# HGD_MCU_v0_1_-20200807.net
KiCad netlist of a schematic drawn in Altium Designer
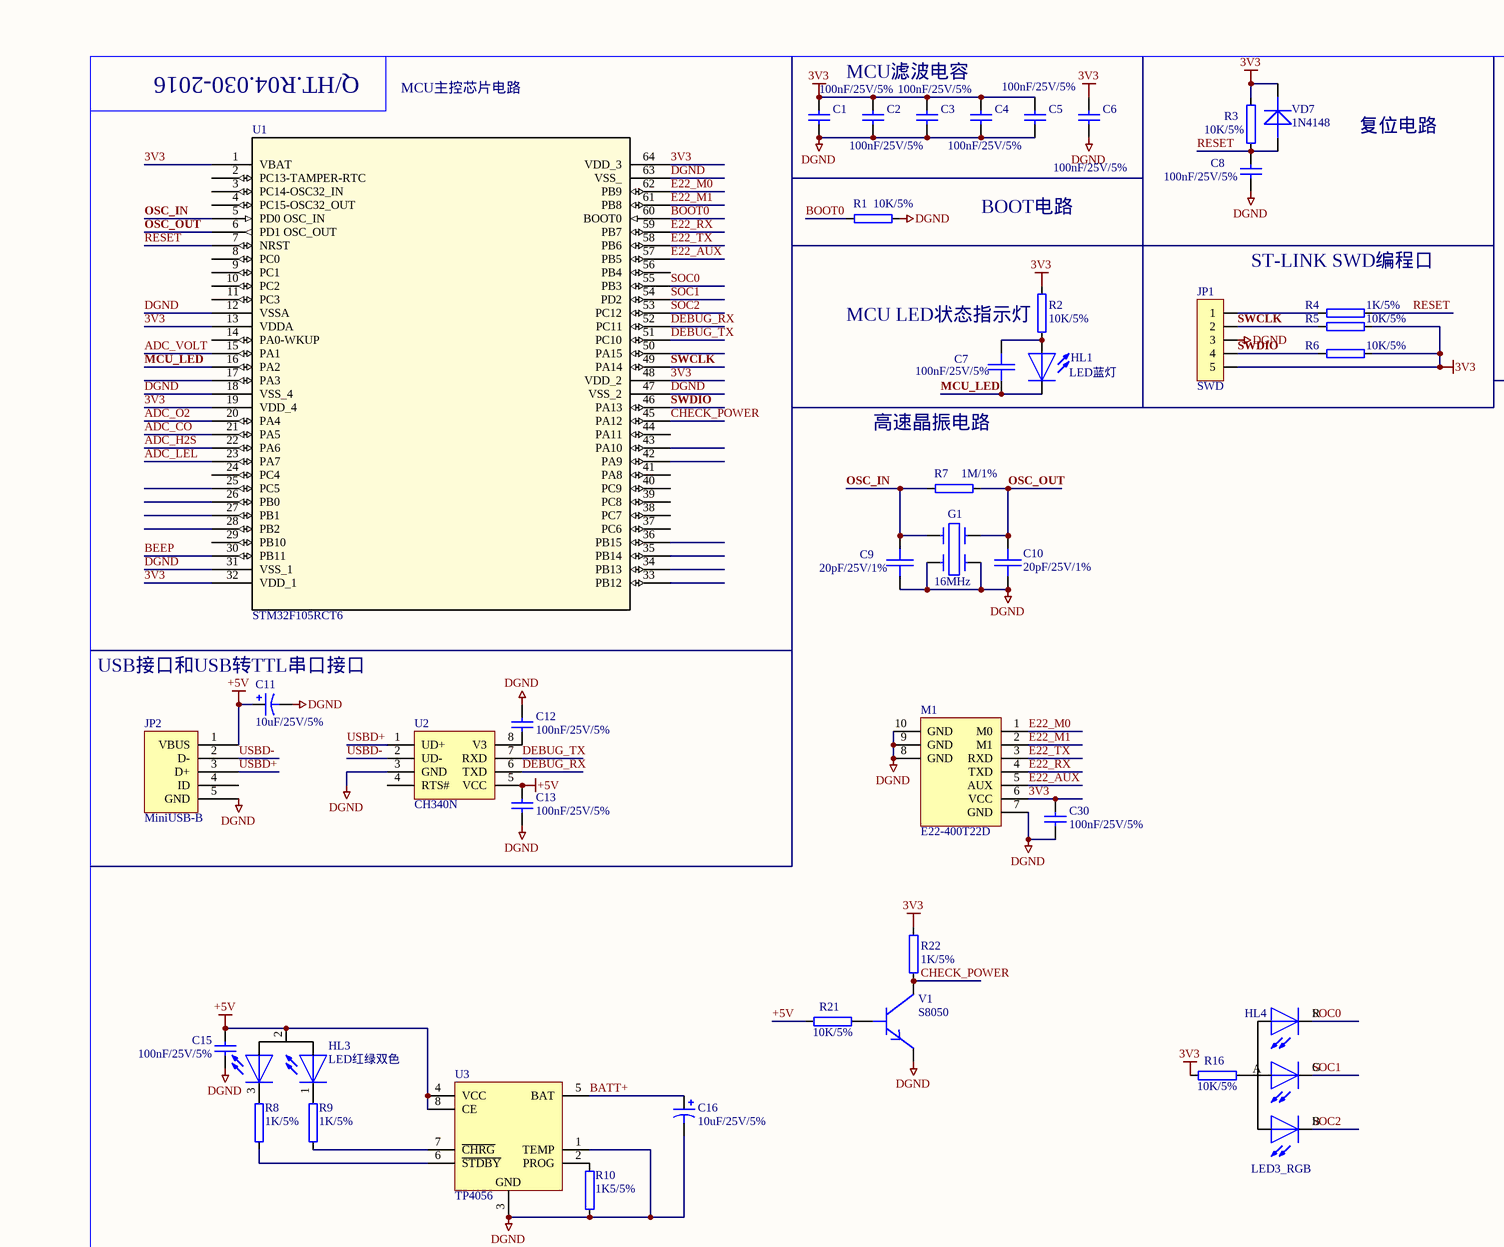
[diagram p0: HGD_MCU(v0.1)-20200807.SchDoc, top left]
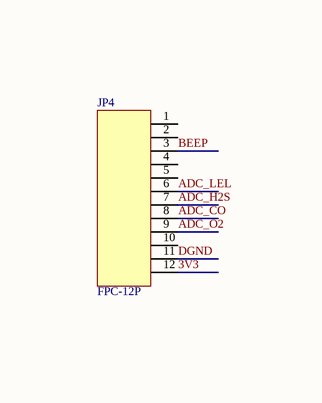
[diagram p1: HGD_MCU(v0.1)-20200807.SchDoc, top right]
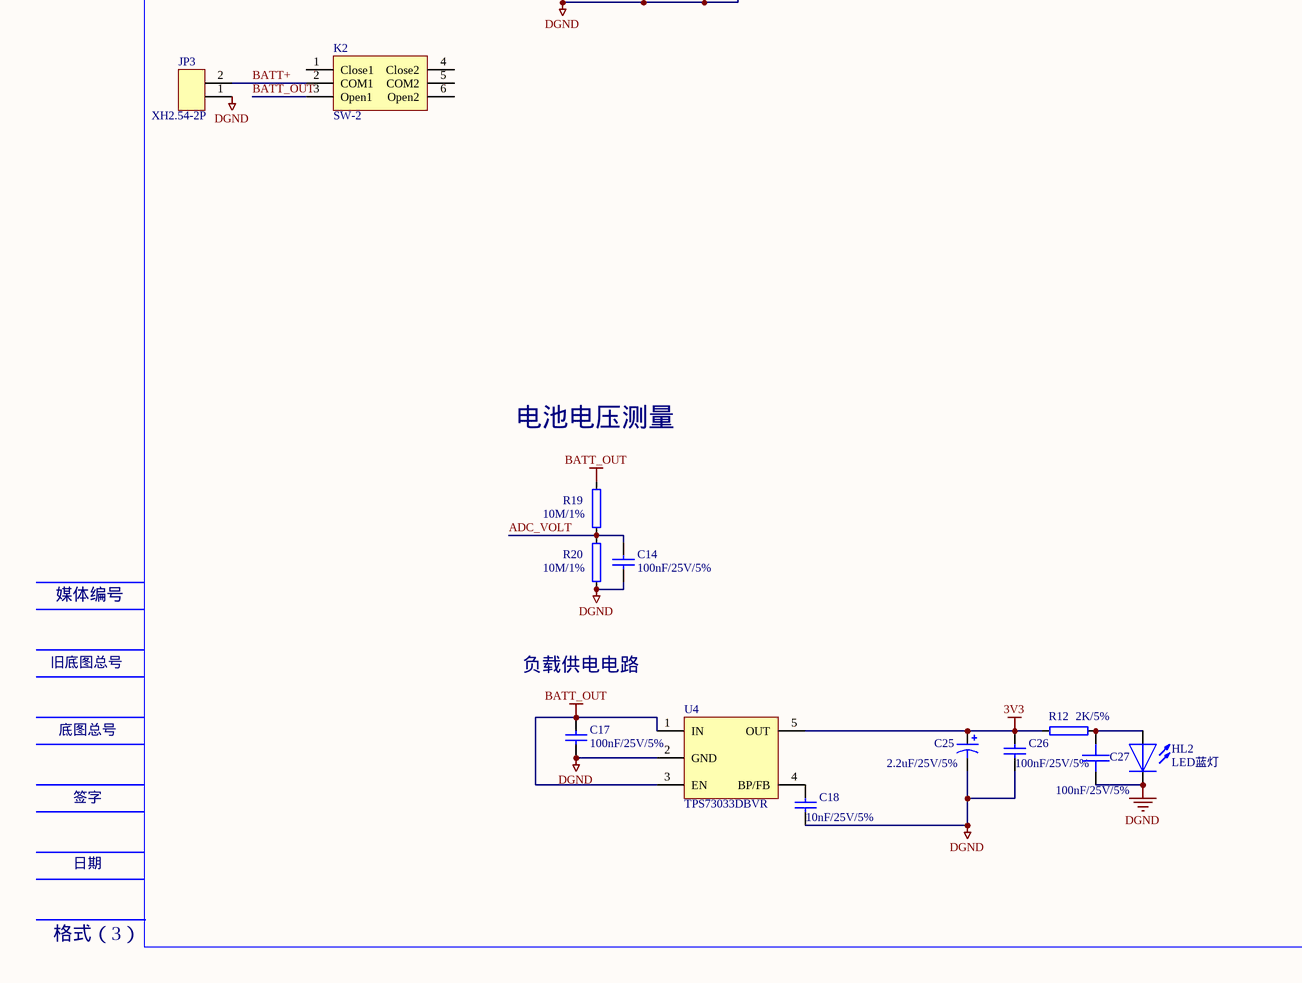
[diagram p2: HGD_MCU(v0.1)-20200807.SchDoc, bottom left]
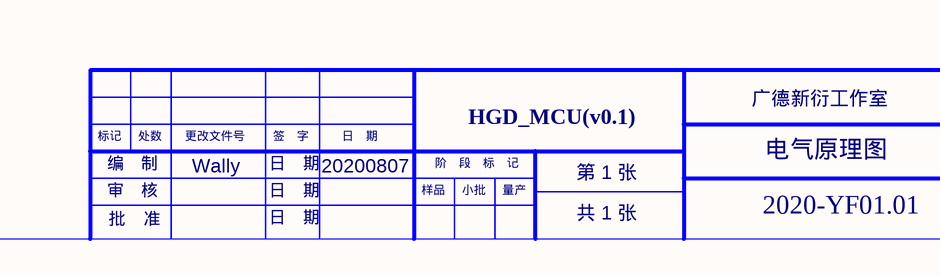
[diagram p3: HGD_MCU(v0.1)-20200807.SchDoc, bottom right]

(export (version "E")
  (design (tool "Eeschema 10.0.6"))
  (components
    (comp (ref "C1")
      (value "100nF/25V/5%")
      (footprint "C0603")
      (description "电容")
      (libsource (lib "*") (part "CAP-SMD"))
    )
    (comp (ref "C2")
      (value "100nF/25V/5%")
      (footprint "C0603")
      (description "电容")
      (libsource (lib "*") (part "CAP-SMD"))
    )
    (comp (ref "C3")
      (value "100nF/25V/5%")
      (footprint "C0603")
      (description "电容")
      (libsource (lib "*") (part "CAP-SMD"))
    )
    (comp (ref "C4")
      (value "100nF/25V/5%")
      (footprint "C0603")
      (description "电容")
      (libsource (lib "*") (part "CAP-SMD"))
    )
    (comp (ref "C5")
      (value "100nF/25V/5%")
      (footprint "C0603")
      (description "电容")
      (libsource (lib "*") (part "CAP-SMD"))
    )
    (comp (ref "C6")
      (value "100nF/25V/5%")
      (footprint "C0603")
      (description "电容")
      (libsource (lib "*") (part "CAP-SMD"))
    )
    (comp (ref "C7")
      (value "100nF/25V/5%")
      (footprint "C0603")
      (description "电容")
      (libsource (lib "*") (part "CAP"))
    )
    (comp (ref "C8")
      (value "100nF/25V/5%")
      (footprint "C0603")
      (description "电容")
      (libsource (lib "*") (part "CAP-SMD"))
    )
    (comp (ref "C9")
      (value "20pF/25V/1%")
      (footprint "C0603")
      (description "电容")
      (libsource (lib "ESSCH-Union") (part "CAP"))
    )
    (comp (ref "C10")
      (value "20pF/25V/1%")
      (footprint "C0603")
      (description "电容")
      (libsource (lib "ESSCH-Union") (part "CAP"))
    )
    (comp (ref "C11")
      (value "10uF/25V/5%")
      (footprint "C1206-1")
      (description "钽电容")
      (fields (field (name "PUBLISHER") "Altium Limited"))
      (libsource (lib "Miscellaneous Devices") (part "Cap Pol1"))
    )
    (comp (ref "C12")
      (value "100nF/25V/5%")
      (footprint "C0603")
      (description "电容")
      (fields (field (name "PUBLISHER") "Altium Limited"))
      (libsource (lib "Miscellaneous Devices") (part "Cap"))
    )
    (comp (ref "C13")
      (value "100nF/25V/5%")
      (footprint "C0603")
      (description "电容")
      (fields (field (name "PUBLISHER") "Altium Limited"))
      (libsource (lib "Miscellaneous Devices") (part "Cap"))
    )
    (comp (ref "C14") (value "100nF/25V/5%") (footprint "C0603") (libsource (lib "*") (part "CAP-SMD")))
    (comp (ref "C15")
      (value "100nF/25V/5%")
      (footprint "C0603")
      (description "电容")
      (fields (field (name "PUBLISHER") "Altium Limited"))
      (libsource (lib "Miscellaneous Devices") (part "Cap"))
    )
    (comp (ref "C16")
      (value "10uF/25V/5%")
      (footprint "C1206-1")
      (description "钽电容")
      (fields (field (name "PUBLISHER") "Altium Limited"))
      (libsource (lib "Miscellaneous Devices") (part "Cap Pol1"))
    )
    (comp (ref "C17") (value "100nF/25V/5%") (footprint "C0603") (libsource (lib "*") (part "CAP-SMD")))
    (comp (ref "C18")
      (value "10nF/25V/5%")
      (footprint "C0603")
      (description "电容")
      (fields (field (name "PUBLISHER") "Altium Limited"))
      (libsource (lib "Miscellaneous Devices") (part "Cap"))
    )
    (comp (ref "C25")
      (value "2.2uF/25V/5%")
      (footprint "C1206-1")
      (description "钽电容")
      (fields (field (name "PUBLISHER") "Altium Limited"))
      (libsource (lib "Miscellaneous Devices") (part "Cap Pol1"))
    )
    (comp (ref "C26")
      (value "100nF/25V/5%")
      (footprint "C0603")
      (description "电容")
      (fields (field (name "PUBLISHER") "Altium Limited"))
      (libsource (lib "Miscellaneous Devices") (part "Cap"))
    )
    (comp (ref "C27")
      (value "100nF/25V/5%")
      (footprint "C0603")
      (description "电容")
      (libsource (lib "*") (part "CAP"))
    )
    (comp (ref "C30")
      (value "100nF/25V/5%")
      (footprint "C0603")
      (description "电容")
      (fields (field (name "PUBLISHER") "Altium Limited"))
      (libsource (lib "Miscellaneous Devices") (part "Cap"))
    )
    (comp (ref "G1")
      (value "16MHz")
      (footprint "OSC5032")
      (description "两对电极压电晶体")
      (libsource (lib "ESSCH-Union") (part "CRYSTAL_4"))
    )
    (comp (ref "HL1")
      (value "LED蓝灯")
      (footprint "LED0603")
      (description "发光二极管")
      (libsource (lib "wypPCB_Lib") (part "发光二极管"))
    )
    (comp (ref "HL2")
      (value "LED蓝灯")
      (footprint "LED0603")
      (description "发光二极管")
      (libsource (lib "wypPCB_Lib") (part "发光二极管"))
    )
    (comp (ref "HL3")
      (value "LED红绿双色")
      (footprint "LED2_Common_Anode")
      (description "LED2_Common_Anode：双色LED，共阳极")
      (libsource (lib "wypPCB_Lib") (part "LED2_Common_Anode"))
    )
    (comp (ref "HL4")
      (value "LED3_RGB")
      (footprint "LED3_Common_Anode")
      (description "LED3_Common_Anode：三色共阳极LED")
      (libsource (lib "wypPCB_Lib") (part "LED3_Common_Anode"))
    )
    (comp (ref "JP1")
      (value "SWD")
      (footprint "XH2.54-5AW")
      (description "XH2.54-5P直插插针")
      (libsource (lib "wypPCB_Lib") (part "JP_XH2.54-5AW"))
    )
    (comp (ref "JP2")
      (value "MiniUSB-B")
      (footprint "MiniUSB-B")
      (description "MiniUSB-B母头插座")
      (libsource (lib "wypPCB_Lib") (part "MiniUSB-B"))
    )
    (comp (ref "JP3")
      (value "XH2.54-2P")
      (footprint "XH2.54-2AW")
      (description "XH2.54-2P弯针插座")
      (libsource (lib "wypPCB_Lib") (part "XH2.54-2AW"))
    )
    (comp (ref "JP4")
      (value "FPC-12P")
      (footprint "FPC-1.0MM-12P-W")
      (libsource (lib "wypPCB_Lib") (part "FPC-12P"))
    )
    (comp (ref "K2")
      (value "SW-2")
      (footprint "BTN-7*7")
      (description "SW-2：2通道自锁开关")
      (libsource (lib "wypPCB_Lib") (part "SW-2"))
    )
    (comp (ref "M1")
      (value "E22-400T22D")
      (footprint "E22-400T22D")
      (description "E22-400T22D LoRa模块")
      (libsource (lib "wypPCB_Lib") (part "E22-400T22D"))
    )
    (comp (ref "R1")
      (value "10K/5%")
      (footprint "R0603")
      (description "电阻")
      (libsource (lib "") (part "RES2_1"))
    )
    (comp (ref "R2")
      (value "10K/5%")
      (footprint "R0603")
      (description "电阻")
      (libsource (lib "") (part "RES2_1"))
    )
    (comp (ref "R3")
      (value "10K/5%")
      (footprint "R0603")
      (description "电阻")
      (libsource (lib "") (part "RES2_2"))
    )
    (comp (ref "R4")
      (value "1K/5%")
      (footprint "R0603")
      (description "电阻")
      (libsource (lib "") (part "RES2_2"))
    )
    (comp (ref "R5")
      (value "10K/5%")
      (footprint "R0603")
      (description "电阻")
      (libsource (lib "") (part "RES2_2"))
    )
    (comp (ref "R6")
      (value "10K/5%")
      (footprint "R0603")
      (description "电阻")
      (libsource (lib "") (part "RES2_2"))
    )
    (comp (ref "R7")
      (value "1M/1%")
      (footprint "R0603")
      (description "电阻")
      (libsource (lib "") (part "RES2_2"))
    )
    (comp (ref "R8")
      (value "1K/5%")
      (footprint "R0603")
      (description "电阻")
      (libsource (lib "*") (part "RES2"))
    )
    (comp (ref "R9")
      (value "1K/5%")
      (footprint "R0603")
      (description "电阻")
      (libsource (lib "*") (part "RES2"))
    )
    (comp (ref "R10")
      (value "1K5/5%")
      (footprint "R0603")
      (description "电阻")
      (libsource (lib "*") (part "RES2"))
    )
    (comp (ref "R12")
      (value "2K/5%")
      (footprint "R0603")
      (description "电阻")
      (libsource (lib "") (part "RES2_1"))
    )
    (comp (ref "R16")
      (value "10K/5%")
      (footprint "R0603")
      (description "电阻")
      (libsource (lib "") (part "RES2_1"))
    )
    (comp (ref "R19")
      (value "10M/1%")
      (footprint "R0603")
      (description "电阻")
      (libsource (lib "") (part "RES2_1"))
    )
    (comp (ref "R20")
      (value "10M/1%")
      (footprint "R0603")
      (description "电阻")
      (libsource (lib "") (part "RES2_1"))
    )
    (comp (ref "R21")
      (value "10K/5%")
      (footprint "R0603")
      (description "电阻")
      (libsource (lib "") (part "RES2_2"))
    )
    (comp (ref "R22")
      (value "1K/5%")
      (footprint "R0603")
      (description "电阻")
      (libsource (lib "*") (part "RES2"))
    )
    (comp (ref "U1")
      (value "STM32F105RCT6")
      (footprint "LQFP64_STM32F105R")
      (libsource (lib "wypPCB_Lib") (part "STM32F105RCT6"))
    )
    (comp (ref "U2")
      (value "CH340N")
      (footprint "CH340N_SOP8")
      (libsource (lib "wypPCB_Lib") (part "CH340N"))
    )
    (comp (ref "U3")
      (value "TP4056")
      (footprint "TP4056_SOP8_SOP127P600X175-8N")
      (libsource (lib "wypPCB_Lib") (part "TP4056"))
    )
    (comp (ref "U4")
      (value "TPS73033DBVR")
      (footprint "SGM2019_SOT23-5_95P280X125-5N")
      (description "SGM2019：Low Power, Low Dropout, RF Linear Regulators")
      (libsource (lib "wypPCB_Lib") (part "SGM2019"))
    )
    (comp (ref "V1")
      (value "S8050")
      (footprint "SOT-23")
      (description "NPN三极管")
      (libsource (lib "ESLIB(v1.1)-AD9-20150731") (part "NPN"))
    )
    (comp (ref "VD7")
      (value "1N4148")
      (footprint "LL-34")
      (description "开关二极管")
      (libsource (lib "wypPCB_Lib") (part "开关二极管"))
    )
  )
  (nets
    (net (code "1") (name "+5V") (class "Default")
      (node (ref "C11") (pin "1") (pinfunction "1_1") (pintype "passive"))
      (node (ref "C13") (pin "1") (pinfunction "1_1") (pintype "passive"))
      (node (ref "C15") (pin "1") (pinfunction "1_1") (pintype "passive"))
      (node (ref "HL3") (pin "2") (pinfunction "A_2") (pintype "passive"))
      (node (ref "JP2") (pin "1") (pinfunction "VBUS_1") (pintype "passive"))
      (node (ref "R21") (pin "2") (pintype "passive"))
      (node (ref "U2") (pin "5") (pinfunction "VCC_5") (pintype "passive"))
      (node (ref "U3") (pin "4") (pinfunction "VCC_4") (pintype "passive"))
      (node (ref "U3") (pin "8") (pinfunction "CE_8") (pintype "passive"))
    )
    (net (code "2") (name "/ADC_CO") (class "Default")
      (node (ref "JP4") (pin "8") (pintype "passive"))
      (node (ref "U1") (pin "21") (pinfunction "PA5_21") (pintype "bidirectional"))
    )
    (net (code "3") (name "/ADC_H2S") (class "Default")
      (node (ref "JP4") (pin "7") (pintype "passive"))
      (node (ref "U1") (pin "22") (pinfunction "PA6_22") (pintype "bidirectional"))
    )
    (net (code "4") (name "/ADC_LEL") (class "Default")
      (node (ref "JP4") (pin "6") (pintype "passive"))
      (node (ref "U1") (pin "23") (pinfunction "PA7_23") (pintype "bidirectional"))
    )
    (net (code "5") (name "/ADC_O2") (class "Default")
      (node (ref "JP4") (pin "9") (pintype "passive"))
      (node (ref "U1") (pin "20") (pinfunction "PA4_20") (pintype "bidirectional"))
    )
    (net (code "6") (name "/ADC_VOLT") (class "Default")
      (node (ref "C14") (pin "1") (pintype "passive"))
      (node (ref "R19") (pin "2") (pintype "passive"))
      (node (ref "R20") (pin "1") (pintype "passive"))
      (node (ref "U1") (pin "15") (pinfunction "PA1_15") (pintype "bidirectional"))
    )
    (net (code "7") (name "/BATT+") (class "Default")
      (node (ref "C16") (pin "1") (pinfunction "1_1") (pintype "passive"))
      (node (ref "JP3") (pin "2") (pintype "passive"))
      (node (ref "K2") (pin "2") (pinfunction "COM1_2") (pintype "passive"))
      (node (ref "U3") (pin "5") (pinfunction "BAT_5") (pintype "passive"))
    )
    (net (code "8") (name "/BEEP") (class "Default")
      (node (ref "JP4") (pin "3") (pintype "passive"))
      (node (ref "U1") (pin "30") (pinfunction "PB11_30") (pintype "bidirectional"))
    )
    (net (code "9") (name "/BOOT0") (class "Default")
      (node (ref "R1") (pin "2") (pintype "passive"))
      (node (ref "U1") (pin "60") (pinfunction "BOOT0_60") (pintype "input"))
    )
    (net (code "10") (name "/CHECK_POWER") (class "Default")
      (node (ref "R22") (pin "2") (pintype "passive"))
      (node (ref "U1") (pin "45") (pinfunction "PA12_45") (pintype "bidirectional"))
      (node (ref "V1") (pin "C") (pintype "passive"))
    )
    (net (code "11") (name "/DEBUG_RX") (class "Default")
      (node (ref "U1") (pin "52") (pinfunction "PC11_52") (pintype "bidirectional"))
      (node (ref "U2") (pin "6") (pinfunction "TXD_6") (pintype "passive"))
    )
    (net (code "12") (name "/DEBUG_TX") (class "Default")
      (node (ref "U1") (pin "51") (pinfunction "PC10_51") (pintype "bidirectional"))
      (node (ref "U2") (pin "7") (pinfunction "RXD_7") (pintype "passive"))
    )
    (net (code "13") (name "/E22_AUX") (class "Default")
      (node (ref "M1") (pin "5") (pinfunction "AUX_5") (pintype "passive"))
      (node (ref "U1") (pin "57") (pinfunction "PB5_57") (pintype "bidirectional"))
    )
    (net (code "14") (name "/E22_M0") (class "Default")
      (node (ref "M1") (pin "1") (pinfunction "M0_1") (pintype "passive"))
      (node (ref "U1") (pin "62") (pinfunction "PB9_62") (pintype "bidirectional"))
    )
    (net (code "15") (name "/E22_M1") (class "Default")
      (node (ref "M1") (pin "2") (pinfunction "M1_2") (pintype "passive"))
      (node (ref "U1") (pin "61") (pinfunction "PB8_61") (pintype "bidirectional"))
    )
    (net (code "16") (name "/E22_RX") (class "Default")
      (node (ref "M1") (pin "4") (pinfunction "TXD_4") (pintype "passive"))
      (node (ref "U1") (pin "59") (pinfunction "PB7_59") (pintype "bidirectional"))
    )
    (net (code "17") (name "/E22_TX") (class "Default")
      (node (ref "M1") (pin "3") (pinfunction "RXD_3") (pintype "passive"))
      (node (ref "U1") (pin "58") (pinfunction "PB6_58") (pintype "bidirectional"))
    )
    (net (code "18") (name "/MCU_LED") (class "Default")
      (node (ref "C7") (pin "2") (pintype "passive"))
      (node (ref "HL1") (pin "K") (pintype "passive"))
      (node (ref "U1") (pin "16") (pinfunction "PA2_16") (pintype "bidirectional"))
    )
    (net (code "19") (name "/OSC_IN") (class "Default")
      (node (ref "C9") (pin "2") (pintype "passive"))
      (node (ref "G1") (pin "1") (pintype "passive"))
      (node (ref "R7") (pin "1") (pintype "passive"))
      (node (ref "U1") (pin "5") (pinfunction "PD0_OSC_IN_5") (pintype "input"))
    )
    (net (code "20") (name "/OSC_OUT") (class "Default")
      (node (ref "C10") (pin "1") (pintype "passive"))
      (node (ref "G1") (pin "3") (pintype "passive"))
      (node (ref "R7") (pin "2") (pintype "passive"))
      (node (ref "U1") (pin "6") (pinfunction "PD1_OSC_OUT_6") (pintype "output"))
    )
    (net (code "21") (name "/RESET") (class "Default")
      (node (ref "C8") (pin "1") (pintype "passive"))
      (node (ref "R3") (pin "1") (pintype "passive"))
      (node (ref "R4") (pin "2") (pintype "passive"))
      (node (ref "U1") (pin "7") (pinfunction "NRST_7") (pintype "bidirectional"))
      (node (ref "VD7") (pin "A") (pintype "passive"))
    )
    (net (code "22") (name "/SOC0") (class "Default")
      (node (ref "HL4") (pin "1") (pinfunction "R_1") (pintype "passive"))
      (node (ref "U1") (pin "55") (pinfunction "PB3_55") (pintype "bidirectional"))
    )
    (net (code "23") (name "/SOC1") (class "Default")
      (node (ref "HL4") (pin "3") (pinfunction "G_3") (pintype "passive"))
      (node (ref "U1") (pin "54") (pinfunction "PD2_54") (pintype "bidirectional"))
    )
    (net (code "24") (name "/SOC2") (class "Default")
      (node (ref "HL4") (pin "4") (pinfunction "B_4") (pintype "passive"))
      (node (ref "U1") (pin "53") (pinfunction "PC12_53") (pintype "bidirectional"))
    )
    (net (code "25") (name "/SWCLK") (class "Default")
      (node (ref "JP1") (pin "2") (pinfunction "2_2") (pintype "passive"))
      (node (ref "R5") (pin "1") (pintype "passive"))
      (node (ref "U1") (pin "49") (pinfunction "PA14_49") (pintype "bidirectional"))
    )
    (net (code "26") (name "/SWDIO") (class "Default")
      (node (ref "JP1") (pin "4") (pinfunction "4_4") (pintype "passive"))
      (node (ref "R6") (pin "1") (pintype "passive"))
      (node (ref "U1") (pin "46") (pinfunction "PA13_46") (pintype "bidirectional"))
    )
    (net (code "27") (name "/USBD+") (class "Default")
      (node (ref "JP2") (pin "3") (pinfunction "D+_3") (pintype "passive"))
      (node (ref "U2") (pin "1") (pinfunction "UD+_1") (pintype "passive"))
    )
    (net (code "28") (name "/USBD-") (class "Default")
      (node (ref "JP2") (pin "2") (pinfunction "D-_2") (pintype "passive"))
      (node (ref "U2") (pin "2") (pinfunction "UD-_2") (pintype "passive"))
    )
    (net (code "29") (name "3V3") (class "Default")
      (node (ref "C1") (pin "2") (pintype "passive"))
      (node (ref "C2") (pin "1") (pintype "passive"))
      (node (ref "C25") (pin "1") (pinfunction "1_1") (pintype "passive"))
      (node (ref "C26") (pin "2") (pinfunction "2_2") (pintype "passive"))
      (node (ref "C3") (pin "1") (pintype "passive"))
      (node (ref "C30") (pin "2") (pinfunction "2_2") (pintype "passive"))
      (node (ref "C4") (pin "2") (pintype "passive"))
      (node (ref "C5") (pin "2") (pintype "passive"))
      (node (ref "C6") (pin "2") (pintype "passive"))
      (node (ref "JP1") (pin "5") (pinfunction "5_5") (pintype "passive"))
      (node (ref "JP4") (pin "12") (pintype "passive"))
      (node (ref "M1") (pin "6") (pinfunction "VCC_6") (pintype "passive"))
      (node (ref "R12") (pin "1") (pintype "passive"))
      (node (ref "R16") (pin "1") (pintype "passive"))
      (node (ref "R2") (pin "1") (pintype "passive"))
      (node (ref "R22") (pin "1") (pintype "passive"))
      (node (ref "R3") (pin "2") (pintype "passive"))
      (node (ref "R5") (pin "2") (pintype "passive"))
      (node (ref "R6") (pin "2") (pintype "passive"))
      (node (ref "U1") (pin "1") (pinfunction "VBAT_1") (pintype "power_in"))
      (node (ref "U1") (pin "13") (pinfunction "VDDA_13") (pintype "power_in"))
      (node (ref "U1") (pin "19") (pinfunction "VDD_4_19") (pintype "power_in"))
      (node (ref "U1") (pin "32") (pinfunction "VDD_1_32") (pintype "power_in"))
      (node (ref "U1") (pin "48") (pinfunction "VDD_2_48") (pintype "power_in"))
      (node (ref "U1") (pin "64") (pinfunction "VDD_3_64") (pintype "power_in"))
      (node (ref "U4") (pin "5") (pinfunction "OUT_5") (pintype "passive"))
      (node (ref "VD7") (pin "K") (pintype "passive"))
    )
    (net (code "30") (name "BATT_OUT") (class "Default")
      (node (ref "C17") (pin "1") (pintype "passive"))
      (node (ref "K2") (pin "3") (pinfunction "Open1_3") (pintype "passive"))
      (node (ref "R19") (pin "1") (pintype "passive"))
      (node (ref "U4") (pin "1") (pinfunction "IN_1") (pintype "passive"))
      (node (ref "U4") (pin "3") (pinfunction "EN_3") (pintype "passive"))
    )
    (net (code "31") (name "DGND") (class "Default")
      (node (ref "C1") (pin "1") (pintype "passive"))
      (node (ref "C10") (pin "2") (pintype "passive"))
      (node (ref "C11") (pin "2") (pinfunction "2_2") (pintype "passive"))
      (node (ref "C12") (pin "1") (pinfunction "1_1") (pintype "passive"))
      (node (ref "C13") (pin "2") (pinfunction "2_2") (pintype "passive"))
      (node (ref "C14") (pin "2") (pintype "passive"))
      (node (ref "C15") (pin "2") (pinfunction "2_2") (pintype "passive"))
      (node (ref "C16") (pin "2") (pinfunction "2_2") (pintype "passive"))
      (node (ref "C17") (pin "2") (pintype "passive"))
      (node (ref "C18") (pin "1") (pinfunction "1_1") (pintype "passive"))
      (node (ref "C2") (pin "2") (pintype "passive"))
      (node (ref "C25") (pin "2") (pinfunction "2_2") (pintype "passive"))
      (node (ref "C26") (pin "1") (pinfunction "1_1") (pintype "passive"))
      (node (ref "C27") (pin "2") (pintype "passive"))
      (node (ref "C3") (pin "2") (pintype "passive"))
      (node (ref "C30") (pin "1") (pinfunction "1_1") (pintype "passive"))
      (node (ref "C4") (pin "1") (pintype "passive"))
      (node (ref "C5") (pin "1") (pintype "passive"))
      (node (ref "C6") (pin "1") (pintype "passive"))
      (node (ref "C8") (pin "2") (pintype "passive"))
      (node (ref "C9") (pin "1") (pintype "passive"))
      (node (ref "G1") (pin "2") (pintype "passive"))
      (node (ref "G1") (pin "4") (pintype "passive"))
      (node (ref "HL2") (pin "K") (pintype "passive"))
      (node (ref "JP1") (pin "3") (pinfunction "3_3") (pintype "passive"))
      (node (ref "JP2") (pin "5") (pinfunction "GND_5") (pintype "passive"))
      (node (ref "JP3") (pin "1") (pintype "passive"))
      (node (ref "JP4") (pin "11") (pintype "passive"))
      (node (ref "M1") (pin "10") (pinfunction "GND_10") (pintype "passive"))
      (node (ref "M1") (pin "7") (pinfunction "GND_7") (pintype "passive"))
      (node (ref "M1") (pin "8") (pinfunction "GND_8") (pintype "passive"))
      (node (ref "M1") (pin "9") (pinfunction "GND_9") (pintype "passive"))
      (node (ref "R1") (pin "1") (pintype "passive"))
      (node (ref "R10") (pin "1") (pintype "passive"))
      (node (ref "R20") (pin "2") (pintype "passive"))
      (node (ref "U1") (pin "12") (pinfunction "VSSA_12") (pintype "power_in"))
      (node (ref "U1") (pin "18") (pinfunction "VSS_4_18") (pintype "power_in"))
      (node (ref "U1") (pin "31") (pinfunction "VSS_1_31") (pintype "power_in"))
      (node (ref "U1") (pin "47") (pinfunction "VSS_2_47") (pintype "power_in"))
      (node (ref "U1") (pin "63") (pinfunction "VSS__63") (pintype "power_in"))
      (node (ref "U2") (pin "3") (pinfunction "GND_3") (pintype "passive"))
      (node (ref "U3") (pin "1") (pinfunction "TEMP_1") (pintype "passive"))
      (node (ref "U3") (pin "3") (pinfunction "GND_3") (pintype "passive"))
      (node (ref "U4") (pin "2") (pinfunction "GND_2") (pintype "passive"))
      (node (ref "V1") (pin "E") (pintype "passive"))
    )
    (net (code "32") (name "Net-(C7-Pad1)") (class "Default")
      (node (ref "C7") (pin "1") (pintype "passive"))
      (node (ref "HL1") (pin "A") (pintype "passive"))
      (node (ref "R2") (pin "2") (pintype "passive"))
    )
    (net (code "33") (name "Net-(C27-Pad1)") (class "Default")
      (node (ref "C27") (pin "1") (pintype "passive"))
      (node (ref "HL2") (pin "A") (pintype "passive"))
      (node (ref "R12") (pin "2") (pintype "passive"))
    )
    (net (code "34") (name "Net-(HL3-K1)") (class "Default")
      (node (ref "HL3") (pin "1") (pinfunction "K1_1") (pintype "passive"))
      (node (ref "R9") (pin "2") (pintype "passive"))
    )
    (net (code "35") (name "Net-(HL3-K2)") (class "Default")
      (node (ref "HL3") (pin "3") (pinfunction "K2_3") (pintype "passive"))
      (node (ref "R8") (pin "2") (pintype "passive"))
    )
    (net (code "36") (name "Net-(HL4-A)") (class "Default")
      (node (ref "HL4") (pin "2") (pinfunction "A_2") (pintype "passive"))
      (node (ref "R16") (pin "2") (pintype "passive"))
    )
    (net (code "37") (name "Net-(JP1-Pad1)") (class "Default")
      (node (ref "JP1") (pin "1") (pinfunction "1_1") (pintype "passive"))
      (node (ref "R4") (pin "1") (pintype "passive"))
    )
    (net (code "38") (name "Net-(R21-Pad1)") (class "Default")
      (node (ref "R21") (pin "1") (pintype "passive"))
      (node (ref "V1") (pin "B") (pintype "passive"))
    )
    (net (code "39") (name "Net-(U2-V3)") (class "Default")
      (node (ref "C12") (pin "2") (pinfunction "2_2") (pintype "passive"))
      (node (ref "U2") (pin "8") (pinfunction "V3_8") (pintype "passive"))
    )
    (net (code "40") (name "Net-(U3-PROG)") (class "Default")
      (node (ref "R10") (pin "2") (pintype "passive"))
      (node (ref "U3") (pin "2") (pinfunction "PROG_2") (pintype "passive"))
    )
    (net (code "41") (name "Net-(U3-~{CHRG})") (class "Default")
      (node (ref "R9") (pin "1") (pintype "passive"))
      (node (ref "U3") (pin "7") (pinfunction "~{CHRG}_7") (pintype "passive"))
    )
    (net (code "42") (name "Net-(U3-~{STDBY})") (class "Default")
      (node (ref "R8") (pin "1") (pintype "passive"))
      (node (ref "U3") (pin "6") (pinfunction "~{STDBY}_6") (pintype "passive"))
    )
    (net (code "43") (name "Net-(U4-BP{slash}FB)") (class "Default")
      (node (ref "C18") (pin "2") (pinfunction "2_2") (pintype "passive"))
      (node (ref "U4") (pin "4") (pinfunction "BP/FB_4") (pintype "passive"))
    )
    (net (code "44") (name "unconnected-(JP2-ID-Pad4)") (class "Default")
      (node (ref "JP2") (pin "4") (pinfunction "ID_4") (pintype "passive"))
    )
    (net (code "45") (name "unconnected-(JP4-Pad1)") (class "Default")
      (node (ref "JP4") (pin "1") (pintype "passive"))
    )
    (net (code "46") (name "unconnected-(JP4-Pad2)") (class "Default")
      (node (ref "JP4") (pin "2") (pintype "passive"))
    )
    (net (code "47") (name "unconnected-(JP4-Pad4)") (class "Default")
      (node (ref "JP4") (pin "4") (pintype "passive"))
    )
    (net (code "48") (name "unconnected-(JP4-Pad5)") (class "Default")
      (node (ref "JP4") (pin "5") (pintype "passive"))
    )
    (net (code "49") (name "unconnected-(JP4-Pad10)") (class "Default")
      (node (ref "JP4") (pin "10") (pintype "passive"))
    )
    (net (code "50") (name "unconnected-(K2-COM2-Pad5)") (class "Default")
      (node (ref "K2") (pin "5") (pinfunction "COM2_5") (pintype "passive"))
    )
    (net (code "51") (name "unconnected-(K2-Close1-Pad1)") (class "Default")
      (node (ref "K2") (pin "1") (pinfunction "Close1_1") (pintype "passive"))
    )
    (net (code "52") (name "unconnected-(K2-Close2-Pad4)") (class "Default")
      (node (ref "K2") (pin "4") (pinfunction "Close2_4") (pintype "passive"))
    )
    (net (code "53") (name "unconnected-(K2-Open2-Pad6)") (class "Default")
      (node (ref "K2") (pin "6") (pinfunction "Open2_6") (pintype "passive"))
    )
    (net (code "54") (name "unconnected-(U1-PA0-WKUP-Pad14)") (class "Default")
      (node (ref "U1") (pin "14") (pinfunction "PA0-WKUP_14") (pintype "bidirectional"))
    )
    (net (code "55") (name "unconnected-(U1-PA3-Pad17)") (class "Default")
      (node (ref "U1") (pin "17") (pinfunction "PA3_17") (pintype "bidirectional"))
    )
    (net (code "56") (name "unconnected-(U1-PA8-Pad41)") (class "Default")
      (node (ref "U1") (pin "41") (pinfunction "PA8_41") (pintype "bidirectional"))
    )
    (net (code "57") (name "unconnected-(U1-PA9-Pad42)") (class "Default")
      (node (ref "U1") (pin "42") (pinfunction "PA9_42") (pintype "bidirectional"))
    )
    (net (code "58") (name "unconnected-(U1-PA10-Pad43)") (class "Default")
      (node (ref "U1") (pin "43") (pinfunction "PA10_43") (pintype "bidirectional"))
    )
    (net (code "59") (name "unconnected-(U1-PA11-Pad44)") (class "Default")
      (node (ref "U1") (pin "44") (pinfunction "PA11_44") (pintype "bidirectional"))
    )
    (net (code "60") (name "unconnected-(U1-PA15-Pad50)") (class "Default")
      (node (ref "U1") (pin "50") (pinfunction "PA15_50") (pintype "bidirectional"))
    )
    (net (code "61") (name "unconnected-(U1-PB0-Pad26)") (class "Default")
      (node (ref "U1") (pin "26") (pinfunction "PB0_26") (pintype "bidirectional"))
    )
    (net (code "62") (name "unconnected-(U1-PB1-Pad27)") (class "Default")
      (node (ref "U1") (pin "27") (pinfunction "PB1_27") (pintype "bidirectional"))
    )
    (net (code "63") (name "unconnected-(U1-PB2-Pad28)") (class "Default")
      (node (ref "U1") (pin "28") (pinfunction "PB2_28") (pintype "bidirectional"))
    )
    (net (code "64") (name "unconnected-(U1-PB4-Pad56)") (class "Default")
      (node (ref "U1") (pin "56") (pinfunction "PB4_56") (pintype "bidirectional"))
    )
    (net (code "65") (name "unconnected-(U1-PB10-Pad29)") (class "Default")
      (node (ref "U1") (pin "29") (pinfunction "PB10_29") (pintype "bidirectional"))
    )
    (net (code "66") (name "unconnected-(U1-PB12-Pad33)") (class "Default")
      (node (ref "U1") (pin "33") (pinfunction "PB12_33") (pintype "bidirectional"))
    )
    (net (code "67") (name "unconnected-(U1-PB13-Pad34)") (class "Default")
      (node (ref "U1") (pin "34") (pinfunction "PB13_34") (pintype "bidirectional"))
    )
    (net (code "68") (name "unconnected-(U1-PB14-Pad35)") (class "Default")
      (node (ref "U1") (pin "35") (pinfunction "PB14_35") (pintype "bidirectional"))
    )
    (net (code "69") (name "unconnected-(U1-PB15-Pad36)") (class "Default")
      (node (ref "U1") (pin "36") (pinfunction "PB15_36") (pintype "bidirectional"))
    )
    (net (code "70") (name "unconnected-(U1-PC0-Pad8)") (class "Default")
      (node (ref "U1") (pin "8") (pinfunction "PC0_8") (pintype "bidirectional"))
    )
    (net (code "71") (name "unconnected-(U1-PC1-Pad9)") (class "Default")
      (node (ref "U1") (pin "9") (pinfunction "PC1_9") (pintype "bidirectional"))
    )
    (net (code "72") (name "unconnected-(U1-PC2-Pad10)") (class "Default")
      (node (ref "U1") (pin "10") (pinfunction "PC2_10") (pintype "bidirectional"))
    )
    (net (code "73") (name "unconnected-(U1-PC3-Pad11)") (class "Default")
      (node (ref "U1") (pin "11") (pinfunction "PC3_11") (pintype "bidirectional"))
    )
    (net (code "74") (name "unconnected-(U1-PC4-Pad24)") (class "Default")
      (node (ref "U1") (pin "24") (pinfunction "PC4_24") (pintype "bidirectional"))
    )
    (net (code "75") (name "unconnected-(U1-PC5-Pad25)") (class "Default")
      (node (ref "U1") (pin "25") (pinfunction "PC5_25") (pintype "bidirectional"))
    )
    (net (code "76") (name "unconnected-(U1-PC6-Pad37)") (class "Default")
      (node (ref "U1") (pin "37") (pinfunction "PC6_37") (pintype "bidirectional"))
    )
    (net (code "77") (name "unconnected-(U1-PC7-Pad38)") (class "Default")
      (node (ref "U1") (pin "38") (pinfunction "PC7_38") (pintype "bidirectional"))
    )
    (net (code "78") (name "unconnected-(U1-PC8-Pad39)") (class "Default")
      (node (ref "U1") (pin "39") (pinfunction "PC8_39") (pintype "bidirectional"))
    )
    (net (code "79") (name "unconnected-(U1-PC9-Pad40)") (class "Default")
      (node (ref "U1") (pin "40") (pinfunction "PC9_40") (pintype "bidirectional"))
    )
    (net (code "80") (name "unconnected-(U1-PC13-TAMPER-RTC-Pad2)") (class "Default")
      (node (ref "U1") (pin "2") (pinfunction "PC13-TAMPER-RTC_2") (pintype "bidirectional"))
    )
    (net (code "81") (name "unconnected-(U1-PC14-OSC32_IN-Pad3)") (class "Default")
      (node (ref "U1") (pin "3") (pinfunction "PC14-OSC32_IN_3") (pintype "bidirectional"))
    )
    (net (code "82") (name "unconnected-(U1-PC15-OSC32_OUT-Pad4)") (class "Default")
      (node (ref "U1") (pin "4") (pinfunction "PC15-OSC32_OUT_4") (pintype "bidirectional"))
    )
    (net (code "83") (name "unconnected-(U2-RTS#-Pad4)") (class "Default")
      (node (ref "U2") (pin "4") (pinfunction "RTS#_4") (pintype "passive"))
    )
  )
)
